# Sensors.net
KiCad netlist of a schematic drawn in Altium Designer
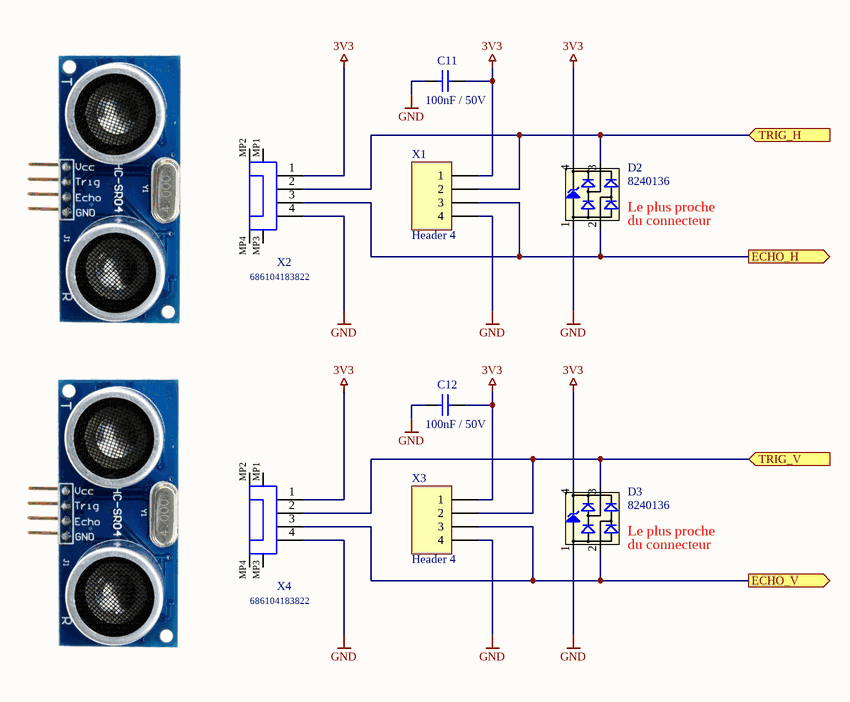
[diagram p0: Sensors.SchDoc]

(export (version "E")
  (design (tool "Eeschema 10.0.6"))
  (components
    (comp (ref "C11")
      (value "100nF / 50V")
      (footprint "CAPC0805")
      (description "Capacitor")
      (fields (field (name "PUBLISHER") "Altium Limited"))
      (libsource (lib "Miscellaneous Devices") (part "Cap"))
    )
    (comp (ref "C12")
      (value "100nF / 50V")
      (footprint "CAPC0805")
      (description "Capacitor")
      (fields (field (name "PUBLISHER") "Altium Limited"))
      (libsource (lib "Miscellaneous Devices") (part "Cap"))
    )
    (comp (ref "D2")
      (value "8240136")
      (footprint "SOT143-4L")
      (description "TVS Diode WE-TVS-HS, VRWM=3.3V")
      (fields (field (name "MANUFACTURER") "Wuerth Elektronik"))
      (libsource (lib "Altium Content Vault") (part "WE-TVS-HS-4"))
    )
    (comp (ref "D3")
      (value "8240136")
      (footprint "SOT143-4L")
      (description "TVS Diode WE-TVS-HS, VRWM=3.3V")
      (fields (field (name "MANUFACTURER") "Wuerth Elektronik"))
      (libsource (lib "Altium Content Vault") (part "WE-TVS-HS-4"))
    )
    (comp (ref "X1")
      (value "Header 4")
      (footprint "Connnector Berg 4P")
      (description "Header, 4-Pin")
      (fields (field (name "PUBLISHER") "Altium Limited"))
      (libsource (lib "Miscellaneous Connectors") (part "Header 4"))
    )
    (comp (ref "X2")
      (value "686104183822")
      (footprint "686104183822")
      (description "SMT ZIF Connectors WR-FPC, Vertical, Type A, pitch 1 mm, 4 pins")
      (fields (field (name "MANUFACTURER") "Wurth Elektronik") (field (name "PUBLISHER") "WurthElektronik"))
      (libsource (lib "Altium Content Vault") (part "WE-686104183822-4"))
    )
    (comp (ref "X3")
      (value "Header 4")
      (footprint "Connnector Berg 4P")
      (description "Header, 4-Pin")
      (fields (field (name "PUBLISHER") "Altium Limited"))
      (libsource (lib "Miscellaneous Connectors") (part "Header 4"))
    )
    (comp (ref "X4")
      (value "686104183822")
      (footprint "686104183822")
      (description "SMT ZIF Connectors WR-FPC, Vertical, Type A, pitch 1 mm, 4 pins")
      (fields (field (name "MANUFACTURER") "Wurth Elektronik") (field (name "PUBLISHER") "WurthElektronik"))
      (libsource (lib "Altium Content Vault") (part "WE-686104183822-4"))
    )
  )
  (nets
    (net (code "1") (name "/ECHO_H") (class "Default")
      (node (ref "D2") (pin "2") (pinfunction "I/O1_2") (pintype "passive"))
      (node (ref "X1") (pin "3") (pinfunction "3_3") (pintype "passive"))
      (node (ref "X2") (pin "3") (pinfunction "3_3") (pintype "passive"))
    )
    (net (code "2") (name "/ECHO_V") (class "Default")
      (node (ref "D3") (pin "2") (pinfunction "I/O1_2") (pintype "passive"))
      (node (ref "X3") (pin "3") (pinfunction "3_3") (pintype "passive"))
      (node (ref "X4") (pin "3") (pinfunction "3_3") (pintype "passive"))
    )
    (net (code "3") (name "/TRIG_H") (class "Default")
      (node (ref "D2") (pin "3") (pinfunction "I/O2_3") (pintype "passive"))
      (node (ref "X1") (pin "2") (pinfunction "2_2") (pintype "passive"))
      (node (ref "X2") (pin "2") (pinfunction "2_2") (pintype "passive"))
    )
    (net (code "4") (name "/TRIG_V") (class "Default")
      (node (ref "D3") (pin "3") (pinfunction "I/O2_3") (pintype "passive"))
      (node (ref "X3") (pin "2") (pinfunction "2_2") (pintype "passive"))
      (node (ref "X4") (pin "2") (pinfunction "2_2") (pintype "passive"))
    )
    (net (code "5") (name "3V3") (class "Default")
      (node (ref "C11") (pin "2") (pinfunction "2_2") (pintype "passive"))
      (node (ref "C12") (pin "2") (pinfunction "2_2") (pintype "passive"))
      (node (ref "D2") (pin "4") (pinfunction "VDD_4") (pintype "passive"))
      (node (ref "D3") (pin "4") (pinfunction "VDD_4") (pintype "passive"))
      (node (ref "X1") (pin "1") (pinfunction "1_1") (pintype "passive"))
      (node (ref "X2") (pin "1") (pinfunction "1_1") (pintype "passive"))
      (node (ref "X3") (pin "1") (pinfunction "1_1") (pintype "passive"))
      (node (ref "X4") (pin "1") (pinfunction "1_1") (pintype "passive"))
    )
    (net (code "6") (name "GND") (class "Default")
      (node (ref "C11") (pin "1") (pinfunction "1_1") (pintype "passive"))
      (node (ref "C12") (pin "1") (pinfunction "1_1") (pintype "passive"))
      (node (ref "D2") (pin "1") (pinfunction "GND_1") (pintype "passive"))
      (node (ref "D3") (pin "1") (pinfunction "GND_1") (pintype "passive"))
      (node (ref "X1") (pin "4") (pinfunction "4_4") (pintype "passive"))
      (node (ref "X2") (pin "4") (pinfunction "4_4") (pintype "passive"))
      (node (ref "X3") (pin "4") (pinfunction "4_4") (pintype "passive"))
      (node (ref "X4") (pin "4") (pinfunction "4_4") (pintype "passive"))
    )
    (net (code "7") (name "unconnected-(X2-PadMP1)") (class "Default")
      (node (ref "X2") (pin "MP1") (pinfunction "MP1_MP1") (pintype "passive"))
    )
    (net (code "8") (name "unconnected-(X2-PadMP2)") (class "Default")
      (node (ref "X2") (pin "MP2") (pinfunction "MP2_MP2") (pintype "passive"))
    )
    (net (code "9") (name "unconnected-(X2-PadMP3)") (class "Default")
      (node (ref "X2") (pin "MP3") (pinfunction "MP3_MP3") (pintype "passive"))
    )
    (net (code "10") (name "unconnected-(X2-PadMP4)") (class "Default")
      (node (ref "X2") (pin "MP4") (pinfunction "MP4_MP4") (pintype "passive"))
    )
    (net (code "11") (name "unconnected-(X4-PadMP1)") (class "Default")
      (node (ref "X4") (pin "MP1") (pinfunction "MP1_MP1") (pintype "passive"))
    )
    (net (code "12") (name "unconnected-(X4-PadMP2)") (class "Default")
      (node (ref "X4") (pin "MP2") (pinfunction "MP2_MP2") (pintype "passive"))
    )
    (net (code "13") (name "unconnected-(X4-PadMP3)") (class "Default")
      (node (ref "X4") (pin "MP3") (pinfunction "MP3_MP3") (pintype "passive"))
    )
    (net (code "14") (name "unconnected-(X4-PadMP4)") (class "Default")
      (node (ref "X4") (pin "MP4") (pinfunction "MP4_MP4") (pintype "passive"))
    )
  )
)
